# LightSensor.net
KiCad netlist of a schematic drawn in Altium Designer
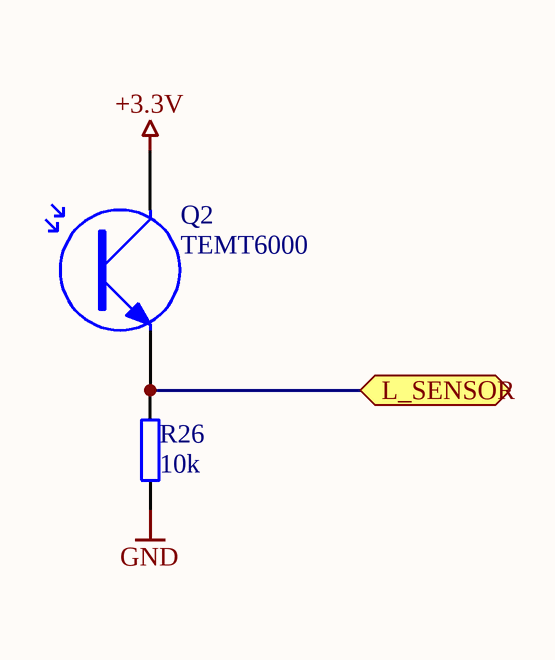
[diagram p0: LightSensor.SchDoc]

(export (version "E")
  (design (tool "Eeschema 10.0.6"))
  (components
    (comp (ref "Q2")
      (value "TEMT6000")
      (footprint "TEMT600")
      (description "Light sensor")
      (libsource (lib "SCH_LIB") (part "TEMT6000"))
    )
    (comp (ref "R26")
      (value "10k")
      (footprint "RES 0805")
      (description "RESISTOR")
      (libsource (lib "SCH_LIB") (part "RES"))
    )
  )
  (nets
    (net (code "1") (name "+3.3V") (class "Default")
      (node (ref "Q2") (pin "1") (pinfunction "C_1") (pintype "passive"))
    )
    (net (code "2") (name "/L_SENSOR") (class "Default")
      (node (ref "Q2") (pin "2") (pinfunction "E_2") (pintype "passive"))
      (node (ref "R26") (pin "1") (pinfunction "1_1") (pintype "passive"))
    )
    (net (code "3") (name "GND") (class "Default")
      (node (ref "R26") (pin "2") (pinfunction "2_2") (pintype "passive"))
    )
  )
)
